# MainMux.net
KiCad netlist of a schematic drawn in Altium Designer
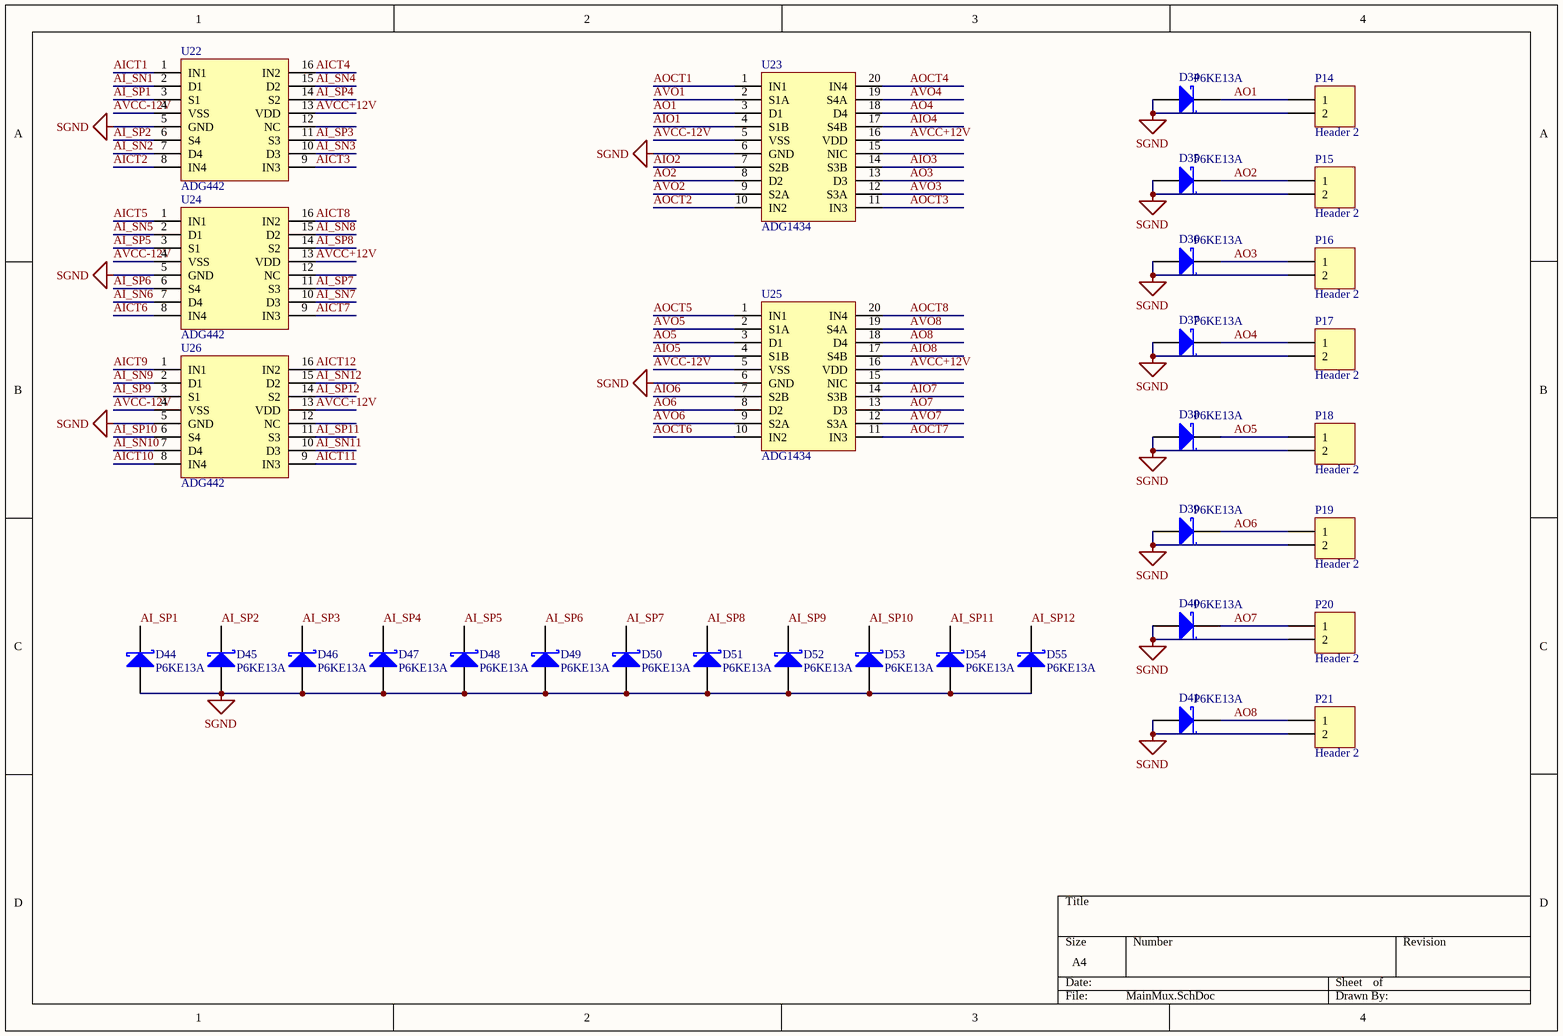
[diagram p0: MainMux.SchDoc]

(export (version "E")
  (design (tool "Eeschema 10.0.6"))
  (components
    (comp (ref "D34")
      (value "P6KE13A")
      (footprint "SMB")
      (description "Schottky Diode")
      (fields (field (name "PUBLISHER") "Altium Limited"))
      (libsource (lib "Miscellaneous Devices") (part "D Schottky"))
    )
    (comp (ref "D35")
      (value "P6KE13A")
      (footprint "SMB")
      (description "Schottky Diode")
      (fields (field (name "PUBLISHER") "Altium Limited"))
      (libsource (lib "Miscellaneous Devices") (part "D Schottky"))
    )
    (comp (ref "D36")
      (value "P6KE13A")
      (footprint "SMB")
      (description "Schottky Diode")
      (fields (field (name "PUBLISHER") "Altium Limited"))
      (libsource (lib "Miscellaneous Devices") (part "D Schottky"))
    )
    (comp (ref "D37")
      (value "P6KE13A")
      (footprint "SMB")
      (description "Schottky Diode")
      (fields (field (name "PUBLISHER") "Altium Limited"))
      (libsource (lib "Miscellaneous Devices") (part "D Schottky"))
    )
    (comp (ref "D38")
      (value "P6KE13A")
      (footprint "SMB")
      (description "Schottky Diode")
      (fields (field (name "PUBLISHER") "Altium Limited"))
      (libsource (lib "Miscellaneous Devices") (part "D Schottky"))
    )
    (comp (ref "D39")
      (value "P6KE13A")
      (footprint "SMB")
      (description "Schottky Diode")
      (fields (field (name "PUBLISHER") "Altium Limited"))
      (libsource (lib "Miscellaneous Devices") (part "D Schottky"))
    )
    (comp (ref "D40")
      (value "P6KE13A")
      (footprint "SMB")
      (description "Schottky Diode")
      (fields (field (name "PUBLISHER") "Altium Limited"))
      (libsource (lib "Miscellaneous Devices") (part "D Schottky"))
    )
    (comp (ref "D41")
      (value "P6KE13A")
      (footprint "SMB")
      (description "Schottky Diode")
      (fields (field (name "PUBLISHER") "Altium Limited"))
      (libsource (lib "Miscellaneous Devices") (part "D Schottky"))
    )
    (comp (ref "D44")
      (value "P6KE13A")
      (footprint "SMB")
      (description "Schottky Diode")
      (fields (field (name "PUBLISHER") "Altium Limited"))
      (libsource (lib "Miscellaneous Devices") (part "D Schottky"))
    )
    (comp (ref "D45")
      (value "P6KE13A")
      (footprint "SMB")
      (description "Schottky Diode")
      (fields (field (name "PUBLISHER") "Altium Limited"))
      (libsource (lib "Miscellaneous Devices") (part "D Schottky"))
    )
    (comp (ref "D46")
      (value "P6KE13A")
      (footprint "SMB")
      (description "Schottky Diode")
      (fields (field (name "PUBLISHER") "Altium Limited"))
      (libsource (lib "Miscellaneous Devices") (part "D Schottky"))
    )
    (comp (ref "D47")
      (value "P6KE13A")
      (footprint "SMB")
      (description "Schottky Diode")
      (fields (field (name "PUBLISHER") "Altium Limited"))
      (libsource (lib "Miscellaneous Devices") (part "D Schottky"))
    )
    (comp (ref "D48")
      (value "P6KE13A")
      (footprint "SMB")
      (description "Schottky Diode")
      (fields (field (name "PUBLISHER") "Altium Limited"))
      (libsource (lib "Miscellaneous Devices") (part "D Schottky"))
    )
    (comp (ref "D49")
      (value "P6KE13A")
      (footprint "SMB")
      (description "Schottky Diode")
      (fields (field (name "PUBLISHER") "Altium Limited"))
      (libsource (lib "Miscellaneous Devices") (part "D Schottky"))
    )
    (comp (ref "D50")
      (value "P6KE13A")
      (footprint "SMB")
      (description "Schottky Diode")
      (fields (field (name "PUBLISHER") "Altium Limited"))
      (libsource (lib "Miscellaneous Devices") (part "D Schottky"))
    )
    (comp (ref "D51")
      (value "P6KE13A")
      (footprint "SMB")
      (description "Schottky Diode")
      (fields (field (name "PUBLISHER") "Altium Limited"))
      (libsource (lib "Miscellaneous Devices") (part "D Schottky"))
    )
    (comp (ref "D52")
      (value "P6KE13A")
      (footprint "SMB")
      (description "Schottky Diode")
      (fields (field (name "PUBLISHER") "Altium Limited"))
      (libsource (lib "Miscellaneous Devices") (part "D Schottky"))
    )
    (comp (ref "D53")
      (value "P6KE13A")
      (footprint "SMB")
      (description "Schottky Diode")
      (fields (field (name "PUBLISHER") "Altium Limited"))
      (libsource (lib "Miscellaneous Devices") (part "D Schottky"))
    )
    (comp (ref "D54")
      (value "P6KE13A")
      (footprint "SMB")
      (description "Schottky Diode")
      (fields (field (name "PUBLISHER") "Altium Limited"))
      (libsource (lib "Miscellaneous Devices") (part "D Schottky"))
    )
    (comp (ref "D55")
      (value "P6KE13A")
      (footprint "SMB")
      (description "Schottky Diode")
      (fields (field (name "PUBLISHER") "Altium Limited"))
      (libsource (lib "Miscellaneous Devices") (part "D Schottky"))
    )
    (comp (ref "P14")
      (value "Header 2")
      (footprint "JIEKE_2PX508")
      (description "Header, 2-Pin")
      (fields (field (name "PUBLISHER") "Altium Limited"))
      (libsource (lib "Miscellaneous Connectors") (part "Header 2"))
    )
    (comp (ref "P15")
      (value "Header 2")
      (footprint "JIEKE_2PX508")
      (description "Header, 2-Pin")
      (fields (field (name "PUBLISHER") "Altium Limited"))
      (libsource (lib "Miscellaneous Connectors") (part "Header 2"))
    )
    (comp (ref "P16")
      (value "Header 2")
      (footprint "JIEKE_2PX508")
      (description "Header, 2-Pin")
      (fields (field (name "PUBLISHER") "Altium Limited"))
      (libsource (lib "Miscellaneous Connectors") (part "Header 2"))
    )
    (comp (ref "P17")
      (value "Header 2")
      (footprint "JIEKE_2PX508")
      (description "Header, 2-Pin")
      (fields (field (name "PUBLISHER") "Altium Limited"))
      (libsource (lib "Miscellaneous Connectors") (part "Header 2"))
    )
    (comp (ref "P18")
      (value "Header 2")
      (footprint "JIEKE_2PX508")
      (description "Header, 2-Pin")
      (fields (field (name "PUBLISHER") "Altium Limited"))
      (libsource (lib "Miscellaneous Connectors") (part "Header 2"))
    )
    (comp (ref "P19")
      (value "Header 2")
      (footprint "JIEKE_2PX508")
      (description "Header, 2-Pin")
      (fields (field (name "PUBLISHER") "Altium Limited"))
      (libsource (lib "Miscellaneous Connectors") (part "Header 2"))
    )
    (comp (ref "P20")
      (value "Header 2")
      (footprint "JIEKE_2PX508")
      (description "Header, 2-Pin")
      (fields (field (name "PUBLISHER") "Altium Limited"))
      (libsource (lib "Miscellaneous Connectors") (part "Header 2"))
    )
    (comp (ref "P21")
      (value "Header 2")
      (footprint "JIEKE_2PX508")
      (description "Header, 2-Pin")
      (fields (field (name "PUBLISHER") "Altium Limited"))
      (libsource (lib "Miscellaneous Connectors") (part "Header 2"))
    )
    (comp (ref "U22")
      (value "ADG442")
      (footprint "SOIC127P600-16M")
      (libsource (lib "斜测仪") (part "ADG441-ADG444"))
    )
    (comp (ref "U23") (value "ADG1434") (footprint "TSSOP20") (libsource (lib "斜测仪") (part "ADG1434")))
    (comp (ref "U24")
      (value "ADG442")
      (footprint "SOIC127P600-16M")
      (libsource (lib "斜测仪") (part "ADG441-ADG444"))
    )
    (comp (ref "U25") (value "ADG1434") (footprint "TSSOP20") (libsource (lib "斜测仪") (part "ADG1434")))
    (comp (ref "U26")
      (value "ADG442")
      (footprint "SOIC127P600-16M")
      (libsource (lib "斜测仪") (part "ADG441-ADG444"))
    )
  )
  (nets
    (net (code "1") (name "/AICT1") (class "Default")
      (node (ref "U22") (pin "1") (pinfunction "IN1_1") (pintype "passive"))
    )
    (net (code "2") (name "/AICT2") (class "Default")
      (node (ref "U22") (pin "8") (pinfunction "IN4_8") (pintype "passive"))
    )
    (net (code "3") (name "/AICT3") (class "Default")
      (node (ref "U22") (pin "9") (pinfunction "IN3_9") (pintype "passive"))
    )
    (net (code "4") (name "/AICT4") (class "Default")
      (node (ref "U22") (pin "16") (pinfunction "IN2_16") (pintype "passive"))
    )
    (net (code "5") (name "/AICT5") (class "Default")
      (node (ref "U24") (pin "1") (pinfunction "IN1_1") (pintype "passive"))
    )
    (net (code "6") (name "/AICT6") (class "Default")
      (node (ref "U24") (pin "8") (pinfunction "IN4_8") (pintype "passive"))
    )
    (net (code "7") (name "/AICT7") (class "Default")
      (node (ref "U24") (pin "9") (pinfunction "IN3_9") (pintype "passive"))
    )
    (net (code "8") (name "/AICT8") (class "Default")
      (node (ref "U24") (pin "16") (pinfunction "IN2_16") (pintype "passive"))
    )
    (net (code "9") (name "/AICT9") (class "Default")
      (node (ref "U26") (pin "1") (pinfunction "IN1_1") (pintype "passive"))
    )
    (net (code "10") (name "/AICT10") (class "Default")
      (node (ref "U26") (pin "8") (pinfunction "IN4_8") (pintype "passive"))
    )
    (net (code "11") (name "/AICT11") (class "Default")
      (node (ref "U26") (pin "9") (pinfunction "IN3_9") (pintype "passive"))
    )
    (net (code "12") (name "/AICT12") (class "Default")
      (node (ref "U26") (pin "16") (pinfunction "IN2_16") (pintype "passive"))
    )
    (net (code "13") (name "/AIO1") (class "Default")
      (node (ref "U23") (pin "4") (pinfunction "S1B_4") (pintype "passive"))
    )
    (net (code "14") (name "/AIO2") (class "Default")
      (node (ref "U23") (pin "7") (pinfunction "S2B_7") (pintype "passive"))
    )
    (net (code "15") (name "/AIO3") (class "Default")
      (node (ref "U23") (pin "14") (pinfunction "S3B_14") (pintype "passive"))
    )
    (net (code "16") (name "/AIO4") (class "Default")
      (node (ref "U23") (pin "17") (pinfunction "S4B_17") (pintype "passive"))
    )
    (net (code "17") (name "/AIO5") (class "Default")
      (node (ref "U25") (pin "4") (pinfunction "S1B_4") (pintype "passive"))
    )
    (net (code "18") (name "/AIO6") (class "Default")
      (node (ref "U25") (pin "7") (pinfunction "S2B_7") (pintype "passive"))
    )
    (net (code "19") (name "/AIO7") (class "Default")
      (node (ref "U25") (pin "14") (pinfunction "S3B_14") (pintype "passive"))
    )
    (net (code "20") (name "/AIO8") (class "Default")
      (node (ref "U25") (pin "17") (pinfunction "S4B_17") (pintype "passive"))
    )
    (net (code "21") (name "/AI_SN1") (class "Default")
      (node (ref "U22") (pin "2") (pinfunction "D1_2") (pintype "passive"))
    )
    (net (code "22") (name "/AI_SN2") (class "Default")
      (node (ref "U22") (pin "7") (pinfunction "D4_7") (pintype "passive"))
    )
    (net (code "23") (name "/AI_SN3") (class "Default")
      (node (ref "U22") (pin "10") (pinfunction "D3_10") (pintype "passive"))
    )
    (net (code "24") (name "/AI_SN4") (class "Default")
      (node (ref "U22") (pin "15") (pinfunction "D2_15") (pintype "passive"))
    )
    (net (code "25") (name "/AI_SN5") (class "Default")
      (node (ref "U24") (pin "2") (pinfunction "D1_2") (pintype "passive"))
    )
    (net (code "26") (name "/AI_SN6") (class "Default")
      (node (ref "U24") (pin "7") (pinfunction "D4_7") (pintype "passive"))
    )
    (net (code "27") (name "/AI_SN7") (class "Default")
      (node (ref "U24") (pin "10") (pinfunction "D3_10") (pintype "passive"))
    )
    (net (code "28") (name "/AI_SN8") (class "Default")
      (node (ref "U24") (pin "15") (pinfunction "D2_15") (pintype "passive"))
    )
    (net (code "29") (name "/AI_SN9") (class "Default")
      (node (ref "U26") (pin "2") (pinfunction "D1_2") (pintype "passive"))
    )
    (net (code "30") (name "/AI_SN10") (class "Default")
      (node (ref "U26") (pin "7") (pinfunction "D4_7") (pintype "passive"))
    )
    (net (code "31") (name "/AI_SN11") (class "Default")
      (node (ref "U26") (pin "10") (pinfunction "D3_10") (pintype "passive"))
    )
    (net (code "32") (name "/AI_SN12") (class "Default")
      (node (ref "U26") (pin "15") (pinfunction "D2_15") (pintype "passive"))
    )
    (net (code "33") (name "/AI_SP1") (class "Default")
      (node (ref "D44") (pin "2") (pinfunction "K_2") (pintype "passive"))
      (node (ref "U22") (pin "3") (pinfunction "S1_3") (pintype "passive"))
    )
    (net (code "34") (name "/AI_SP2") (class "Default")
      (node (ref "D45") (pin "2") (pinfunction "K_2") (pintype "passive"))
      (node (ref "U22") (pin "6") (pinfunction "S4_6") (pintype "passive"))
    )
    (net (code "35") (name "/AI_SP3") (class "Default")
      (node (ref "D46") (pin "2") (pinfunction "K_2") (pintype "passive"))
      (node (ref "U22") (pin "11") (pinfunction "S3_11") (pintype "passive"))
    )
    (net (code "36") (name "/AI_SP4") (class "Default")
      (node (ref "D47") (pin "2") (pinfunction "K_2") (pintype "passive"))
      (node (ref "U22") (pin "14") (pinfunction "S2_14") (pintype "passive"))
    )
    (net (code "37") (name "/AI_SP5") (class "Default")
      (node (ref "D48") (pin "2") (pinfunction "K_2") (pintype "passive"))
      (node (ref "U24") (pin "3") (pinfunction "S1_3") (pintype "passive"))
    )
    (net (code "38") (name "/AI_SP6") (class "Default")
      (node (ref "D49") (pin "2") (pinfunction "K_2") (pintype "passive"))
      (node (ref "U24") (pin "6") (pinfunction "S4_6") (pintype "passive"))
    )
    (net (code "39") (name "/AI_SP7") (class "Default")
      (node (ref "D50") (pin "2") (pinfunction "K_2") (pintype "passive"))
      (node (ref "U24") (pin "11") (pinfunction "S3_11") (pintype "passive"))
    )
    (net (code "40") (name "/AI_SP8") (class "Default")
      (node (ref "D51") (pin "2") (pinfunction "K_2") (pintype "passive"))
      (node (ref "U24") (pin "14") (pinfunction "S2_14") (pintype "passive"))
    )
    (net (code "41") (name "/AI_SP9") (class "Default")
      (node (ref "D52") (pin "2") (pinfunction "K_2") (pintype "passive"))
      (node (ref "U26") (pin "3") (pinfunction "S1_3") (pintype "passive"))
    )
    (net (code "42") (name "/AI_SP10") (class "Default")
      (node (ref "D53") (pin "2") (pinfunction "K_2") (pintype "passive"))
      (node (ref "U26") (pin "6") (pinfunction "S4_6") (pintype "passive"))
    )
    (net (code "43") (name "/AI_SP11") (class "Default")
      (node (ref "D54") (pin "2") (pinfunction "K_2") (pintype "passive"))
      (node (ref "U26") (pin "11") (pinfunction "S3_11") (pintype "passive"))
    )
    (net (code "44") (name "/AI_SP12") (class "Default")
      (node (ref "D55") (pin "2") (pinfunction "K_2") (pintype "passive"))
      (node (ref "U26") (pin "14") (pinfunction "S2_14") (pintype "passive"))
    )
    (net (code "45") (name "/AO1") (class "Default")
      (node (ref "D34") (pin "2") (pinfunction "K_2") (pintype "passive"))
      (node (ref "P14") (pin "1") (pinfunction "1_1") (pintype "passive"))
      (node (ref "U23") (pin "3") (pinfunction "D1_3") (pintype "passive"))
    )
    (net (code "46") (name "/AO2") (class "Default")
      (node (ref "D35") (pin "2") (pinfunction "K_2") (pintype "passive"))
      (node (ref "P15") (pin "1") (pinfunction "1_1") (pintype "passive"))
      (node (ref "U23") (pin "8") (pinfunction "D2_8") (pintype "passive"))
    )
    (net (code "47") (name "/AO3") (class "Default")
      (node (ref "D36") (pin "2") (pinfunction "K_2") (pintype "passive"))
      (node (ref "P16") (pin "1") (pinfunction "1_1") (pintype "passive"))
      (node (ref "U23") (pin "13") (pinfunction "D3_13") (pintype "passive"))
    )
    (net (code "48") (name "/AO4") (class "Default")
      (node (ref "D37") (pin "2") (pinfunction "K_2") (pintype "passive"))
      (node (ref "P17") (pin "1") (pinfunction "1_1") (pintype "passive"))
      (node (ref "U23") (pin "18") (pinfunction "D4_18") (pintype "passive"))
    )
    (net (code "49") (name "/AO5") (class "Default")
      (node (ref "D38") (pin "2") (pinfunction "K_2") (pintype "passive"))
      (node (ref "P18") (pin "1") (pinfunction "1_1") (pintype "passive"))
      (node (ref "U25") (pin "3") (pinfunction "D1_3") (pintype "passive"))
    )
    (net (code "50") (name "/AO6") (class "Default")
      (node (ref "D39") (pin "2") (pinfunction "K_2") (pintype "passive"))
      (node (ref "P19") (pin "1") (pinfunction "1_1") (pintype "passive"))
      (node (ref "U25") (pin "8") (pinfunction "D2_8") (pintype "passive"))
    )
    (net (code "51") (name "/AO7") (class "Default")
      (node (ref "D40") (pin "2") (pinfunction "K_2") (pintype "passive"))
      (node (ref "P20") (pin "1") (pinfunction "1_1") (pintype "passive"))
      (node (ref "U25") (pin "13") (pinfunction "D3_13") (pintype "passive"))
    )
    (net (code "52") (name "/AO8") (class "Default")
      (node (ref "D41") (pin "2") (pinfunction "K_2") (pintype "passive"))
      (node (ref "P21") (pin "1") (pinfunction "1_1") (pintype "passive"))
      (node (ref "U25") (pin "18") (pinfunction "D4_18") (pintype "passive"))
    )
    (net (code "53") (name "/AOCT1") (class "Default")
      (node (ref "U23") (pin "1") (pinfunction "IN1_1") (pintype "passive"))
    )
    (net (code "54") (name "/AOCT2") (class "Default")
      (node (ref "U23") (pin "10") (pinfunction "IN2_10") (pintype "passive"))
    )
    (net (code "55") (name "/AOCT3") (class "Default")
      (node (ref "U23") (pin "11") (pinfunction "IN3_11") (pintype "passive"))
    )
    (net (code "56") (name "/AOCT4") (class "Default")
      (node (ref "U23") (pin "20") (pinfunction "IN4_20") (pintype "passive"))
    )
    (net (code "57") (name "/AOCT5") (class "Default")
      (node (ref "U25") (pin "1") (pinfunction "IN1_1") (pintype "passive"))
    )
    (net (code "58") (name "/AOCT6") (class "Default")
      (node (ref "U25") (pin "10") (pinfunction "IN2_10") (pintype "passive"))
    )
    (net (code "59") (name "/AOCT7") (class "Default")
      (node (ref "U25") (pin "11") (pinfunction "IN3_11") (pintype "passive"))
    )
    (net (code "60") (name "/AOCT8") (class "Default")
      (node (ref "U25") (pin "20") (pinfunction "IN4_20") (pintype "passive"))
    )
    (net (code "61") (name "/AVCC+12V") (class "Default")
      (node (ref "U22") (pin "13") (pinfunction "VDD_13") (pintype "passive"))
      (node (ref "U23") (pin "16") (pinfunction "VDD_16") (pintype "passive"))
      (node (ref "U24") (pin "13") (pinfunction "VDD_13") (pintype "passive"))
      (node (ref "U25") (pin "16") (pinfunction "VDD_16") (pintype "passive"))
      (node (ref "U26") (pin "13") (pinfunction "VDD_13") (pintype "passive"))
    )
    (net (code "62") (name "/AVCC-12V") (class "Default")
      (node (ref "U22") (pin "4") (pinfunction "VSS_4") (pintype "passive"))
      (node (ref "U23") (pin "5") (pinfunction "VSS_5") (pintype "passive"))
      (node (ref "U24") (pin "4") (pinfunction "VSS_4") (pintype "passive"))
      (node (ref "U25") (pin "5") (pinfunction "VSS_5") (pintype "passive"))
      (node (ref "U26") (pin "4") (pinfunction "VSS_4") (pintype "passive"))
    )
    (net (code "63") (name "/AVO1") (class "Default")
      (node (ref "U23") (pin "2") (pinfunction "S1A_2") (pintype "passive"))
    )
    (net (code "64") (name "/AVO2") (class "Default")
      (node (ref "U23") (pin "9") (pinfunction "S2A_9") (pintype "passive"))
    )
    (net (code "65") (name "/AVO3") (class "Default")
      (node (ref "U23") (pin "12") (pinfunction "S3A_12") (pintype "passive"))
    )
    (net (code "66") (name "/AVO4") (class "Default")
      (node (ref "U23") (pin "19") (pinfunction "S4A_19") (pintype "passive"))
    )
    (net (code "67") (name "/AVO5") (class "Default")
      (node (ref "U25") (pin "2") (pinfunction "S1A_2") (pintype "passive"))
    )
    (net (code "68") (name "/AVO6") (class "Default")
      (node (ref "U25") (pin "9") (pinfunction "S2A_9") (pintype "passive"))
    )
    (net (code "69") (name "/AVO7") (class "Default")
      (node (ref "U25") (pin "12") (pinfunction "S3A_12") (pintype "passive"))
    )
    (net (code "70") (name "/AVO8") (class "Default")
      (node (ref "U25") (pin "19") (pinfunction "S4A_19") (pintype "passive"))
    )
    (net (code "71") (name "SGND") (class "Default")
      (node (ref "D34") (pin "1") (pinfunction "A_1") (pintype "passive"))
      (node (ref "D35") (pin "1") (pinfunction "A_1") (pintype "passive"))
      (node (ref "D36") (pin "1") (pinfunction "A_1") (pintype "passive"))
      (node (ref "D37") (pin "1") (pinfunction "A_1") (pintype "passive"))
      (node (ref "D38") (pin "1") (pinfunction "A_1") (pintype "passive"))
      (node (ref "D39") (pin "1") (pinfunction "A_1") (pintype "passive"))
      (node (ref "D40") (pin "1") (pinfunction "A_1") (pintype "passive"))
      (node (ref "D41") (pin "1") (pinfunction "A_1") (pintype "passive"))
      (node (ref "D44") (pin "1") (pinfunction "A_1") (pintype "passive"))
      (node (ref "D45") (pin "1") (pinfunction "A_1") (pintype "passive"))
      (node (ref "D46") (pin "1") (pinfunction "A_1") (pintype "passive"))
      (node (ref "D47") (pin "1") (pinfunction "A_1") (pintype "passive"))
      (node (ref "D48") (pin "1") (pinfunction "A_1") (pintype "passive"))
      (node (ref "D49") (pin "1") (pinfunction "A_1") (pintype "passive"))
      (node (ref "D50") (pin "1") (pinfunction "A_1") (pintype "passive"))
      (node (ref "D51") (pin "1") (pinfunction "A_1") (pintype "passive"))
      (node (ref "D52") (pin "1") (pinfunction "A_1") (pintype "passive"))
      (node (ref "D53") (pin "1") (pinfunction "A_1") (pintype "passive"))
      (node (ref "D54") (pin "1") (pinfunction "A_1") (pintype "passive"))
      (node (ref "D55") (pin "1") (pinfunction "A_1") (pintype "passive"))
      (node (ref "P14") (pin "2") (pinfunction "2_2") (pintype "passive"))
      (node (ref "P15") (pin "2") (pinfunction "2_2") (pintype "passive"))
      (node (ref "P16") (pin "2") (pinfunction "2_2") (pintype "passive"))
      (node (ref "P17") (pin "2") (pinfunction "2_2") (pintype "passive"))
      (node (ref "P18") (pin "2") (pinfunction "2_2") (pintype "passive"))
      (node (ref "P19") (pin "2") (pinfunction "2_2") (pintype "passive"))
      (node (ref "P20") (pin "2") (pinfunction "2_2") (pintype "passive"))
      (node (ref "P21") (pin "2") (pinfunction "2_2") (pintype "passive"))
      (node (ref "U22") (pin "5") (pinfunction "GND_5") (pintype "passive"))
      (node (ref "U23") (pin "6") (pinfunction "GND_6") (pintype "passive"))
      (node (ref "U24") (pin "5") (pinfunction "GND_5") (pintype "passive"))
      (node (ref "U25") (pin "6") (pinfunction "GND_6") (pintype "passive"))
      (node (ref "U26") (pin "5") (pinfunction "GND_5") (pintype "passive"))
    )
    (net (code "72") (name "unconnected-(U22-NC-Pad12)") (class "Default")
      (node (ref "U22") (pin "12") (pinfunction "NC_12") (pintype "passive"))
    )
    (net (code "73") (name "unconnected-(U23-NIC-Pad15)") (class "Default")
      (node (ref "U23") (pin "15") (pinfunction "NIC_15") (pintype "passive"))
    )
    (net (code "74") (name "unconnected-(U24-NC-Pad12)") (class "Default")
      (node (ref "U24") (pin "12") (pinfunction "NC_12") (pintype "passive"))
    )
    (net (code "75") (name "unconnected-(U25-NIC-Pad15)") (class "Default")
      (node (ref "U25") (pin "15") (pinfunction "NIC_15") (pintype "passive"))
    )
    (net (code "76") (name "unconnected-(U26-NC-Pad12)") (class "Default")
      (node (ref "U26") (pin "12") (pinfunction "NC_12") (pintype "passive"))
    )
  )
)
